# freq_meter_final.net
KiCad netlist of a schematic drawn in EAGLE
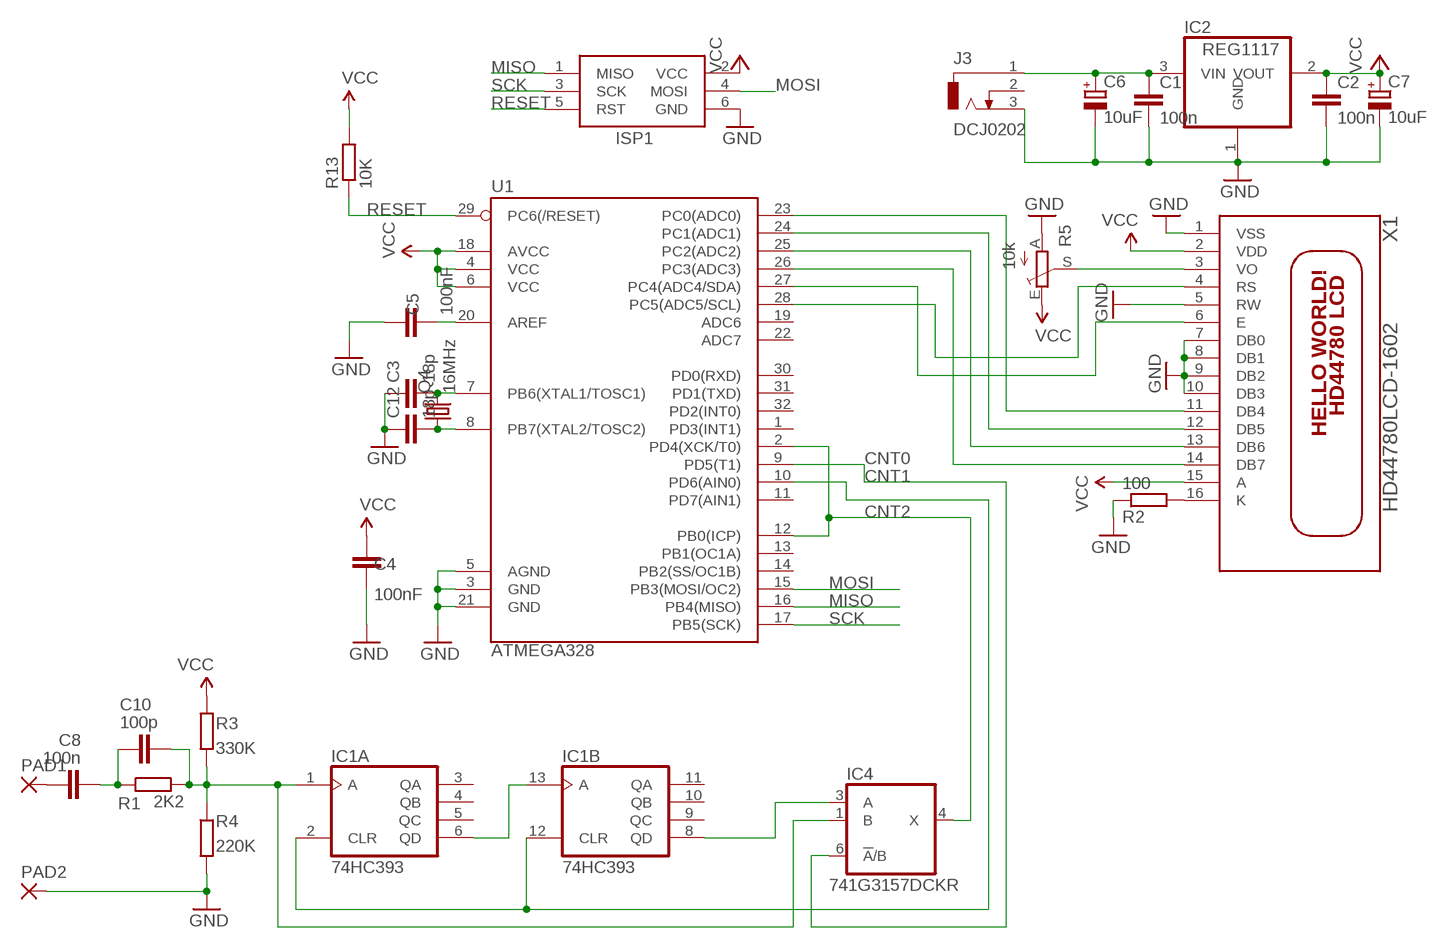
[diagram p0: schematic, sheet 1]

(export (version "E")
  (design (tool "Eeschema 10.0.6"))
  (components
    (comp (ref "C1")
      (value "100n")
      (footprint "eagle-import:C0805")
      (libsource (lib "eagle-import") (part "rcl_334_C-EUC0805"))
    )
    (comp (ref "C2")
      (value "100n")
      (footprint "eagle-import:C0805")
      (libsource (lib "eagle-import") (part "rcl_334_C-EUC0805"))
    )
    (comp (ref "C3")
      (value "18p")
      (footprint "eagle-import:C0805")
      (libsource (lib "eagle-import") (part "C-EUC0805"))
    )
    (comp (ref "C4")
      (value "100nF")
      (footprint "eagle-import:C0805")
      (libsource (lib "eagle-import") (part "resistor_C-EUC0805"))
    )
    (comp (ref "C5")
      (value "100nF")
      (footprint "eagle-import:C0805")
      (libsource (lib "eagle-import") (part "resistor_C-EUC0805"))
    )
    (comp (ref "C6")
      (value "10uF")
      (footprint "eagle-import:SMC_E")
      (libsource (lib "eagle-import") (part "CPOL-EUSMCE"))
    )
    (comp (ref "C7")
      (value "10uF")
      (footprint "eagle-import:SMC_E")
      (libsource (lib "eagle-import") (part "CPOL-EUSMCE"))
    )
    (comp (ref "C8")
      (value "100n")
      (footprint "eagle-import:C0805")
      (libsource (lib "eagle-import") (part "rcl_334_C-EUC0805"))
    )
    (comp (ref "C10")
      (value "100p")
      (footprint "eagle-import:C0805")
      (libsource (lib "eagle-import") (part "rcl_334_C-EUC0805"))
    )
    (comp (ref "C12")
      (value "18p")
      (footprint "eagle-import:C0805")
      (libsource (lib "eagle-import") (part "C-EUC0805"))
    )
    (comp (ref "IC1")
      (value "74HC393")
      (footprint "eagle-import:DIL14")
      (libsource (lib "eagle-import") (part "74393NHCT"))
    )
    (comp (ref "IC2")
      (value "REG1117")
      (footprint "eagle-import:SOT223")
      (libsource (lib "eagle-import") (part "REG1117"))
    )
    (comp (ref "IC4")
      (value "741G3157DCKR")
      (footprint "eagle-import:DCK_R-PDSO-G6")
      (libsource (lib "eagle-import") (part "741G3157DCKR"))
    )
    (comp (ref "ISP1")
      (value "AVRISP-6")
      (footprint "eagle-import:AVRISP")
      (libsource (lib "eagle-import") (part "AVRISP-6"))
    )
    (comp (ref "J3")
      (value "DCJ0202")
      (footprint "eagle-import:DCJ0202")
      (libsource (lib "eagle-import") (part "DCJ0202"))
    )
    (comp (ref "PAD1")
      (value "3,81/1,1")
      (footprint "eagle-import:3,81_1,1")
      (libsource (lib "eagle-import") (part "3,81/1,1"))
    )
    (comp (ref "PAD2")
      (value "3,81/1,1")
      (footprint "eagle-import:3,81_1,1")
      (libsource (lib "eagle-import") (part "3,81/1,1"))
    )
    (comp (ref "Q4")
      (value "16MHz")
      (footprint "eagle-import:HC49UP")
      (libsource (lib "eagle-import") (part "CRYSTALHC49UP"))
    )
    (comp (ref "R1")
      (value "2K2")
      (footprint "eagle-import:R0805")
      (libsource (lib "eagle-import") (part "R-EU_R0805"))
    )
    (comp (ref "R2")
      (value "100")
      (footprint "eagle-import:R0805")
      (libsource (lib "eagle-import") (part "resistor_R-EU_R0805"))
    )
    (comp (ref "R3")
      (value "330K")
      (footprint "eagle-import:R0805")
      (libsource (lib "eagle-import") (part "R-EU_R0805"))
    )
    (comp (ref "R4")
      (value "220K")
      (footprint "eagle-import:R0805")
      (libsource (lib "eagle-import") (part "R-EU_R0805"))
    )
    (comp (ref "R5")
      (value "10k")
      (footprint "eagle-import:CA6V")
      (libsource (lib "eagle-import") (part "TRIM_EU-CA6V"))
    )
    (comp (ref "R13")
      (value "10K")
      (footprint "eagle-import:R0805")
      (libsource (lib "eagle-import") (part "resistor_R-EU_R0805"))
    )
    (comp (ref "U1")
      (value "ATMEGA328")
      (footprint "eagle-import:TQFP32-08")
      (libsource (lib "eagle-import") (part "ATMEGA168"))
    )
    (comp (ref "X1")
      (value "HD44780LCD-1602")
      (footprint "eagle-import:LCD1602")
      (libsource (lib "eagle-import") (part "HD44780LCD-1602"))
    )
  )
  (nets
    (net (code "1") (name "CNT0") (class "Default")
      (node (ref "IC4") (pin "6") (pinfunction "~{A}/B_6") (pintype "input"))
      (node (ref "U1") (pin "9") (pinfunction "PD5(T1)_9") (pintype "bidirectional"))
    )
    (net (code "2") (name "CNT1") (class "Default")
      (node (ref "IC1") (pin "12") (pinfunction "CLR_12") (pintype "input"))
      (node (ref "IC1") (pin "2") (pinfunction "CLR_2") (pintype "input"))
      (node (ref "U1") (pin "10") (pinfunction "PD6(AIN0)_10") (pintype "bidirectional"))
    )
    (net (code "3") (name "CNT2") (class "Default")
      (node (ref "IC4") (pin "4") (pinfunction "X_4") (pintype "bidirectional"))
      (node (ref "U1") (pin "12") (pinfunction "PB0(ICP)_12") (pintype "bidirectional"))
      (node (ref "U1") (pin "2") (pinfunction "PD4(XCK/T0)_2") (pintype "bidirectional"))
    )
    (net (code "4") (name "GND") (class "Default")
      (node (ref "C1") (pin "2") (pinfunction "2_2") (pintype "passive"))
      (node (ref "C12") (pin "1") (pinfunction "1_1") (pintype "passive"))
      (node (ref "C2") (pin "2") (pinfunction "2_2") (pintype "passive"))
      (node (ref "C3") (pin "1") (pinfunction "1_1") (pintype "passive"))
      (node (ref "C4") (pin "1") (pinfunction "1_1") (pintype "passive"))
      (node (ref "C5") (pin "2") (pinfunction "2_2") (pintype "passive"))
      (node (ref "C6") (pin "-") (pinfunction "-_-") (pintype "passive"))
      (node (ref "C7") (pin "-") (pinfunction "-_-") (pintype "passive"))
      (node (ref "IC2") (pin "1") (pinfunction "GND_1") (pintype "power_in"))
      (node (ref "ISP1") (pin "6") (pinfunction "GND_6") (pintype "power_in"))
      (node (ref "J3") (pin "3") (pinfunction "3_3") (pintype "passive"))
      (node (ref "PAD2") (pin "1") (pinfunction "P_1") (pintype "passive"))
      (node (ref "R2") (pin "1") (pinfunction "1_1") (pintype "passive"))
      (node (ref "R4") (pin "2") (pinfunction "2_2") (pintype "passive"))
      (node (ref "R5") (pin "A") (pinfunction "A_A") (pintype "passive"))
      (node (ref "U1") (pin "21") (pinfunction "GND_21") (pintype "bidirectional"))
      (node (ref "U1") (pin "3") (pinfunction "GND_3") (pintype "bidirectional"))
      (node (ref "U1") (pin "5") (pinfunction "AGND_5") (pintype "bidirectional"))
      (node (ref "X1") (pin "1") (pinfunction "VSS_1") (pintype "power_in"))
      (node (ref "X1") (pin "10") (pinfunction "DB3_10") (pintype "bidirectional"))
      (node (ref "X1") (pin "5") (pinfunction "RW_5") (pintype "input"))
      (node (ref "X1") (pin "7") (pinfunction "DB0_7") (pintype "bidirectional"))
      (node (ref "X1") (pin "8") (pinfunction "DB1_8") (pintype "bidirectional"))
      (node (ref "X1") (pin "9") (pinfunction "DB2_9") (pintype "bidirectional"))
    )
    (net (code "5") (name "MISO") (class "Default")
      (node (ref "ISP1") (pin "1") (pinfunction "MISO_1") (pintype "input"))
      (node (ref "U1") (pin "16") (pinfunction "PB4(MISO)_16") (pintype "bidirectional"))
    )
    (net (code "6") (name "MOSI") (class "Default")
      (node (ref "ISP1") (pin "4") (pinfunction "MOSI_4") (pintype "output"))
      (node (ref "U1") (pin "15") (pinfunction "PB3(MOSI/OC2)_15") (pintype "bidirectional"))
    )
    (net (code "7") (name "Net-(C10-Pad2)") (class "Default")
      (node (ref "C10") (pin "2") (pinfunction "2_2") (pintype "passive"))
      (node (ref "C8") (pin "2") (pinfunction "2_2") (pintype "passive"))
      (node (ref "R1") (pin "1") (pinfunction "1_1") (pintype "passive"))
    )
    (net (code "8") (name "Net-(IC1A-A)") (class "Default")
      (node (ref "C10") (pin "1") (pinfunction "1_1") (pintype "passive"))
      (node (ref "IC1") (pin "1") (pinfunction "A_1") (pintype "input"))
      (node (ref "IC4") (pin "1") (pinfunction "B_1") (pintype "bidirectional"))
      (node (ref "R1") (pin "2") (pinfunction "2_2") (pintype "passive"))
      (node (ref "R3") (pin "1") (pinfunction "1_1") (pintype "passive"))
      (node (ref "R4") (pin "1") (pinfunction "1_1") (pintype "passive"))
    )
    (net (code "9") (name "Net-(IC1A-QD)") (class "Default")
      (node (ref "IC1") (pin "13") (pinfunction "A_13") (pintype "input"))
      (node (ref "IC1") (pin "6") (pinfunction "QD_6") (pintype "output"))
    )
    (net (code "10") (name "Net-(IC1B-QD)") (class "Default")
      (node (ref "IC1") (pin "8") (pinfunction "QD_8") (pintype "output"))
      (node (ref "IC4") (pin "3") (pinfunction "A_3") (pintype "bidirectional"))
    )
    (net (code "11") (name "Net-(IC2-VIN)") (class "Default")
      (node (ref "C1") (pin "1") (pinfunction "1_1") (pintype "passive"))
      (node (ref "C6") (pin "+") (pinfunction "+_+") (pintype "passive"))
      (node (ref "IC2") (pin "3") (pinfunction "VIN_3") (pintype "input"))
      (node (ref "J3") (pin "1") (pinfunction "1_1") (pintype "passive"))
    )
    (net (code "12") (name "Net-(PAD1-P)") (class "Default")
      (node (ref "C8") (pin "1") (pinfunction "1_1") (pintype "passive"))
      (node (ref "PAD1") (pin "1") (pinfunction "P_1") (pintype "passive"))
    )
    (net (code "13") (name "Net-(U1-AREF)") (class "Default")
      (node (ref "C5") (pin "1") (pinfunction "1_1") (pintype "passive"))
      (node (ref "U1") (pin "20") (pinfunction "AREF_20") (pintype "bidirectional"))
    )
    (net (code "14") (name "Net-(U1-PB6(XTAL1{slash}TOSC1))") (class "Default")
      (node (ref "C3") (pin "2") (pinfunction "2_2") (pintype "passive"))
      (node (ref "Q4") (pin "2") (pinfunction "2_2") (pintype "passive"))
      (node (ref "U1") (pin "7") (pinfunction "PB6(XTAL1/TOSC1)_7") (pintype "bidirectional"))
    )
    (net (code "15") (name "Net-(U1-PB7(XTAL2{slash}TOSC2))") (class "Default")
      (node (ref "C12") (pin "2") (pinfunction "2_2") (pintype "passive"))
      (node (ref "Q4") (pin "1") (pinfunction "1_1") (pintype "passive"))
      (node (ref "U1") (pin "8") (pinfunction "PB7(XTAL2/TOSC2)_8") (pintype "bidirectional"))
    )
    (net (code "16") (name "Net-(U1-PC0(ADC0))") (class "Default")
      (node (ref "U1") (pin "23") (pinfunction "PC0(ADC0)_23") (pintype "bidirectional"))
      (node (ref "X1") (pin "11") (pinfunction "DB4_11") (pintype "bidirectional"))
    )
    (net (code "17") (name "Net-(U1-PC1(ADC1))") (class "Default")
      (node (ref "U1") (pin "24") (pinfunction "PC1(ADC1)_24") (pintype "bidirectional"))
      (node (ref "X1") (pin "12") (pinfunction "DB5_12") (pintype "bidirectional"))
    )
    (net (code "18") (name "Net-(U1-PC2(ADC2))") (class "Default")
      (node (ref "U1") (pin "25") (pinfunction "PC2(ADC2)_25") (pintype "bidirectional"))
      (node (ref "X1") (pin "13") (pinfunction "DB6_13") (pintype "bidirectional"))
    )
    (net (code "19") (name "Net-(U1-PC3(ADC3))") (class "Default")
      (node (ref "U1") (pin "26") (pinfunction "PC3(ADC3)_26") (pintype "bidirectional"))
      (node (ref "X1") (pin "14") (pinfunction "DB7_14") (pintype "bidirectional"))
    )
    (net (code "20") (name "Net-(U1-PC4(ADC4{slash}SDA))") (class "Default")
      (node (ref "U1") (pin "27") (pinfunction "PC4(ADC4/SDA)_27") (pintype "bidirectional"))
      (node (ref "X1") (pin "6") (pinfunction "E_6") (pintype "input"))
    )
    (net (code "21") (name "Net-(U1-PC5(ADC5{slash}SCL))") (class "Default")
      (node (ref "U1") (pin "28") (pinfunction "PC5(ADC5/SCL)_28") (pintype "bidirectional"))
      (node (ref "X1") (pin "4") (pinfunction "RS_4") (pintype "input"))
    )
    (net (code "22") (name "Net-(X1-K)") (class "Default")
      (node (ref "R2") (pin "2") (pinfunction "2_2") (pintype "passive"))
      (node (ref "X1") (pin "16") (pinfunction "K_16") (pintype "input"))
    )
    (net (code "23") (name "Net-(X1-VO)") (class "Default")
      (node (ref "R5") (pin "S") (pinfunction "S_S") (pintype "passive"))
      (node (ref "X1") (pin "3") (pinfunction "VO_3") (pintype "input"))
    )
    (net (code "24") (name "RESET") (class "Default")
      (node (ref "ISP1") (pin "5") (pinfunction "RST_5") (pintype "output"))
      (node (ref "R13") (pin "1") (pinfunction "1_1") (pintype "passive"))
      (node (ref "U1") (pin "29") (pinfunction "PC6(/RESET)_29") (pintype "bidirectional"))
    )
    (net (code "25") (name "SCK") (class "Default")
      (node (ref "ISP1") (pin "3") (pinfunction "SCK_3") (pintype "output"))
      (node (ref "U1") (pin "17") (pinfunction "PB5(SCK)_17") (pintype "bidirectional"))
    )
    (net (code "26") (name "VCC") (class "Default")
      (node (ref "C2") (pin "1") (pinfunction "1_1") (pintype "passive"))
      (node (ref "C4") (pin "2") (pinfunction "2_2") (pintype "passive"))
      (node (ref "C7") (pin "+") (pinfunction "+_+") (pintype "passive"))
      (node (ref "IC2") (pin "2") (pinfunction "VOUT_2") (pintype "output"))
      (node (ref "ISP1") (pin "2") (pinfunction "VCC_2") (pintype "power_in"))
      (node (ref "R13") (pin "2") (pinfunction "2_2") (pintype "passive"))
      (node (ref "R3") (pin "2") (pinfunction "2_2") (pintype "passive"))
      (node (ref "R5") (pin "E") (pinfunction "E_E") (pintype "passive"))
      (node (ref "U1") (pin "18") (pinfunction "AVCC_18") (pintype "bidirectional"))
      (node (ref "U1") (pin "4") (pinfunction "VCC_4") (pintype "bidirectional"))
      (node (ref "U1") (pin "6") (pinfunction "VCC_6") (pintype "bidirectional"))
      (node (ref "X1") (pin "15") (pinfunction "A_15") (pintype "input"))
      (node (ref "X1") (pin "2") (pinfunction "VDD_2") (pintype "power_in"))
    )
    (net (code "27") (name "unconnected-(IC1A-QA-Pad3)") (class "Default")
      (node (ref "IC1") (pin "3") (pinfunction "QA_3") (pintype "output"))
    )
    (net (code "28") (name "unconnected-(IC1A-QB-Pad4)") (class "Default")
      (node (ref "IC1") (pin "4") (pinfunction "QB_4") (pintype "output"))
    )
    (net (code "29") (name "unconnected-(IC1A-QC-Pad5)") (class "Default")
      (node (ref "IC1") (pin "5") (pinfunction "QC_5") (pintype "output"))
    )
    (net (code "30") (name "unconnected-(IC1B-QA-Pad11)") (class "Default")
      (node (ref "IC1") (pin "11") (pinfunction "QA_11") (pintype "output"))
    )
    (net (code "31") (name "unconnected-(IC1B-QB-Pad10)") (class "Default")
      (node (ref "IC1") (pin "10") (pinfunction "QB_10") (pintype "output"))
    )
    (net (code "32") (name "unconnected-(IC1B-QC-Pad9)") (class "Default")
      (node (ref "IC1") (pin "9") (pinfunction "QC_9") (pintype "output"))
    )
    (net (code "33") (name "unconnected-(J3-Pad2)") (class "Default")
      (node (ref "J3") (pin "2") (pinfunction "2_2") (pintype "passive"))
    )
    (net (code "34") (name "unconnected-(U1-ADC6-Pad19)") (class "Default")
      (node (ref "U1") (pin "19") (pinfunction "ADC6_19") (pintype "bidirectional"))
    )
    (net (code "35") (name "unconnected-(U1-ADC7-Pad22)") (class "Default")
      (node (ref "U1") (pin "22") (pinfunction "ADC7_22") (pintype "bidirectional"))
    )
    (net (code "36") (name "unconnected-(U1-PB1(OC1A)-Pad13)") (class "Default")
      (node (ref "U1") (pin "13") (pinfunction "PB1(OC1A)_13") (pintype "bidirectional"))
    )
    (net (code "37") (name "unconnected-(U1-PB2(SS{slash}OC1B)-Pad14)") (class "Default")
      (node (ref "U1") (pin "14") (pinfunction "PB2(SS/OC1B)_14") (pintype "bidirectional"))
    )
    (net (code "38") (name "unconnected-(U1-PD0(RXD)-Pad30)") (class "Default")
      (node (ref "U1") (pin "30") (pinfunction "PD0(RXD)_30") (pintype "bidirectional"))
    )
    (net (code "39") (name "unconnected-(U1-PD1(TXD)-Pad31)") (class "Default")
      (node (ref "U1") (pin "31") (pinfunction "PD1(TXD)_31") (pintype "bidirectional"))
    )
    (net (code "40") (name "unconnected-(U1-PD2(INT0)-Pad32)") (class "Default")
      (node (ref "U1") (pin "32") (pinfunction "PD2(INT0)_32") (pintype "bidirectional"))
    )
    (net (code "41") (name "unconnected-(U1-PD3(INT1)-Pad1)") (class "Default")
      (node (ref "U1") (pin "1") (pinfunction "PD3(INT1)_1") (pintype "bidirectional"))
    )
    (net (code "42") (name "unconnected-(U1-PD7(AIN1)-Pad11)") (class "Default")
      (node (ref "U1") (pin "11") (pinfunction "PD7(AIN1)_11") (pintype "bidirectional"))
    )
  )
)
